# boardv2power.net
KiCad netlist of a schematic drawn in EAGLE
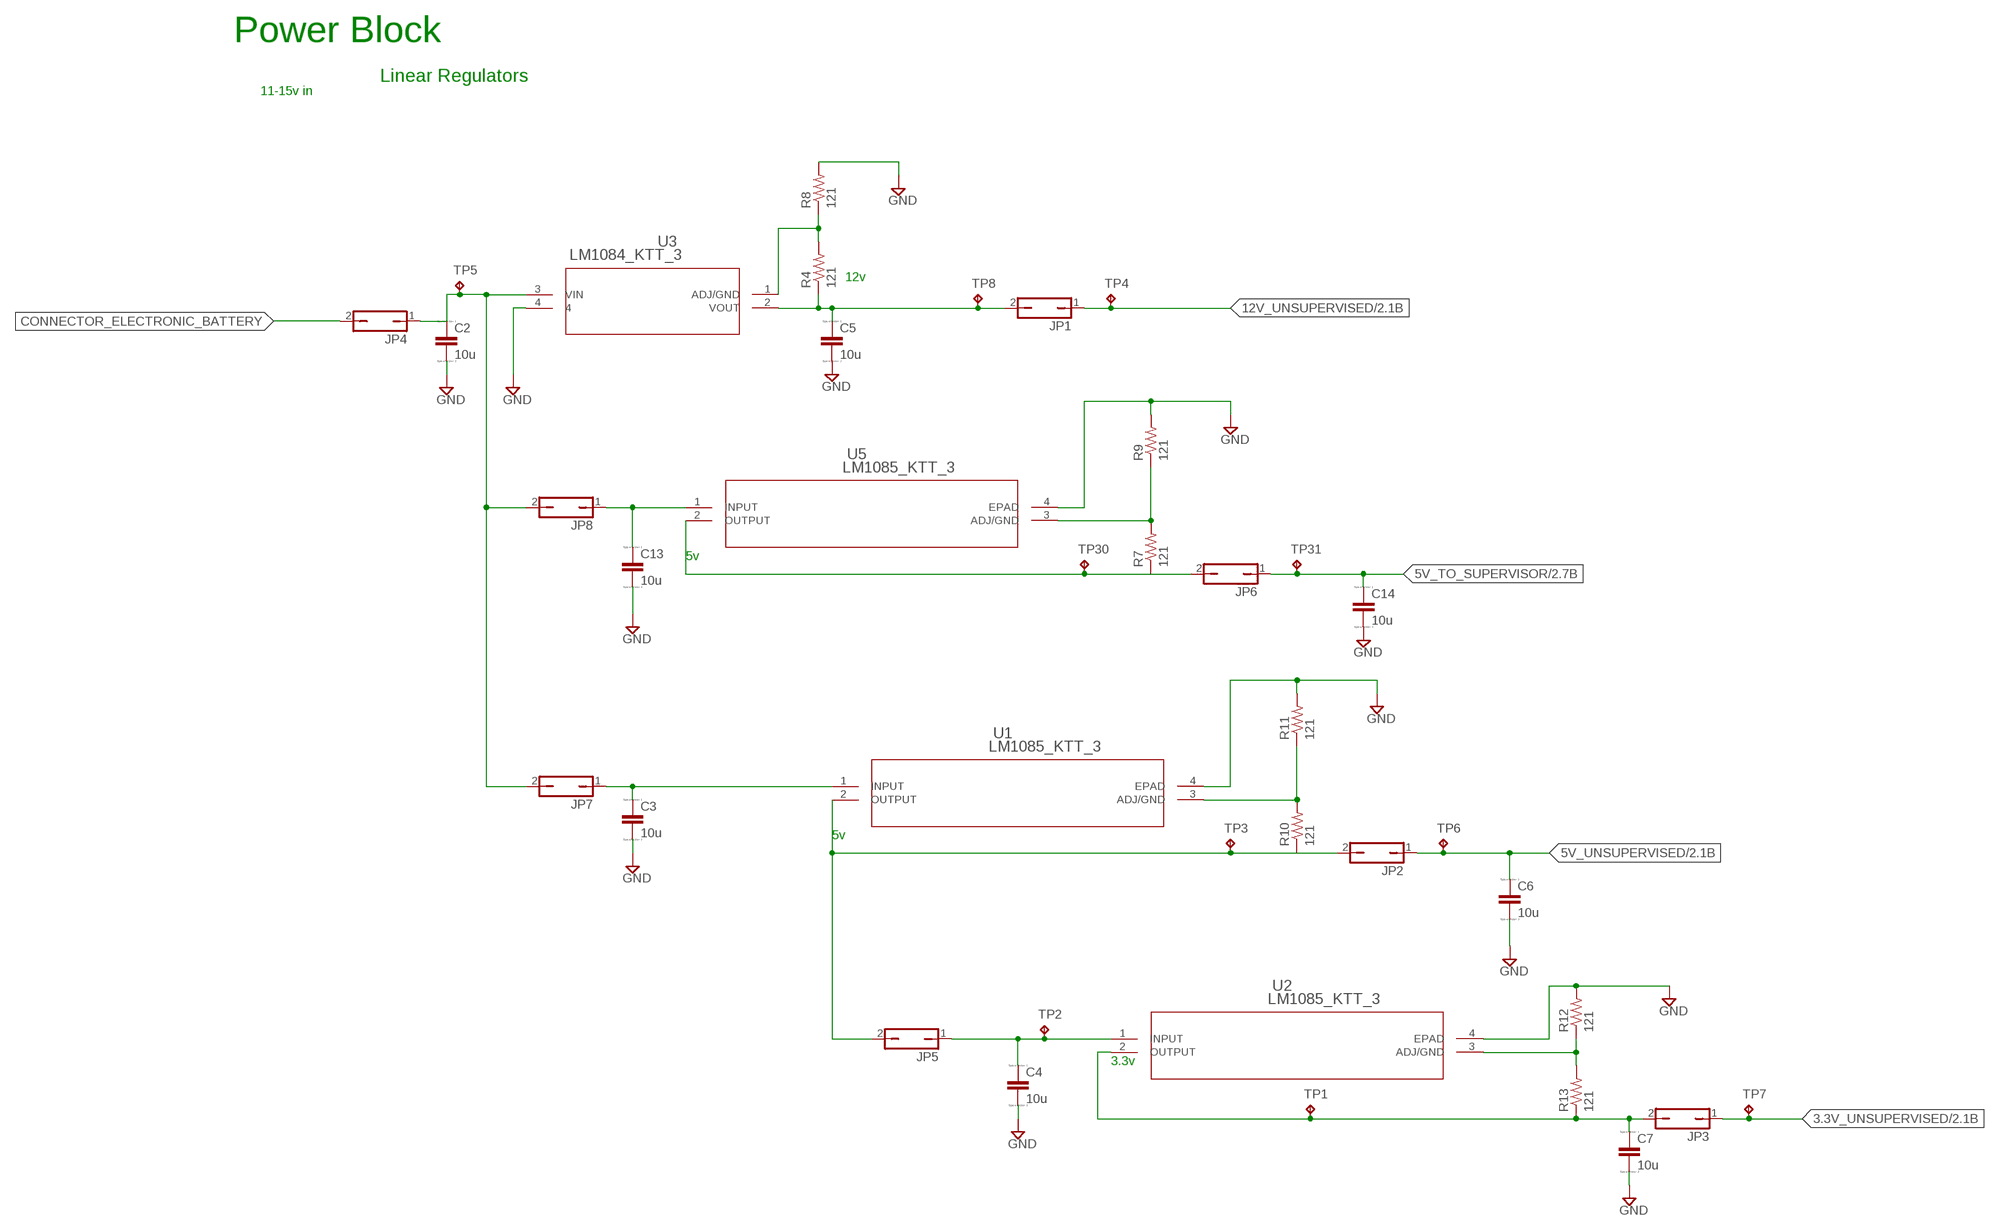
[diagram p0: schematic, sheet 1]
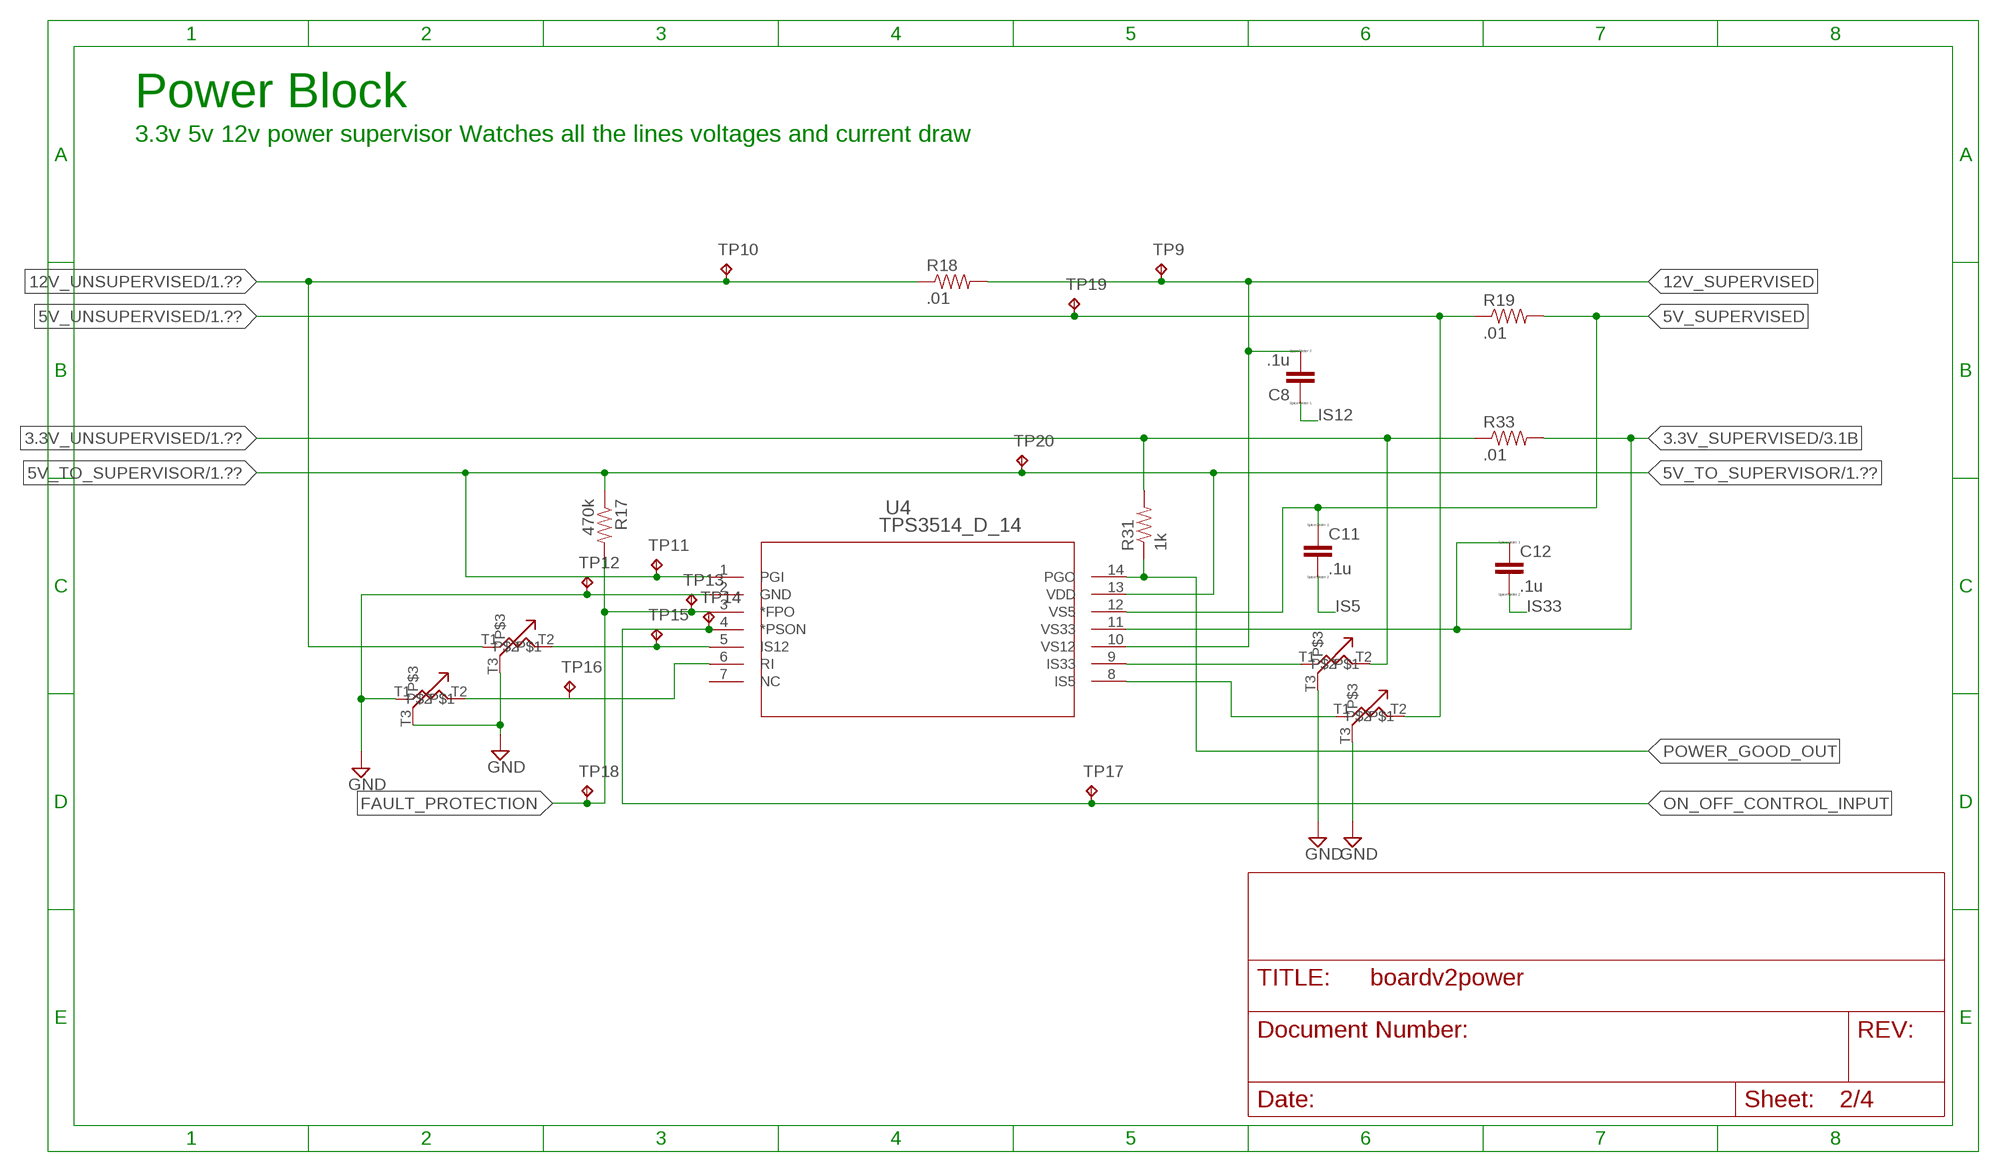
[diagram p1: schematic, sheet 2]
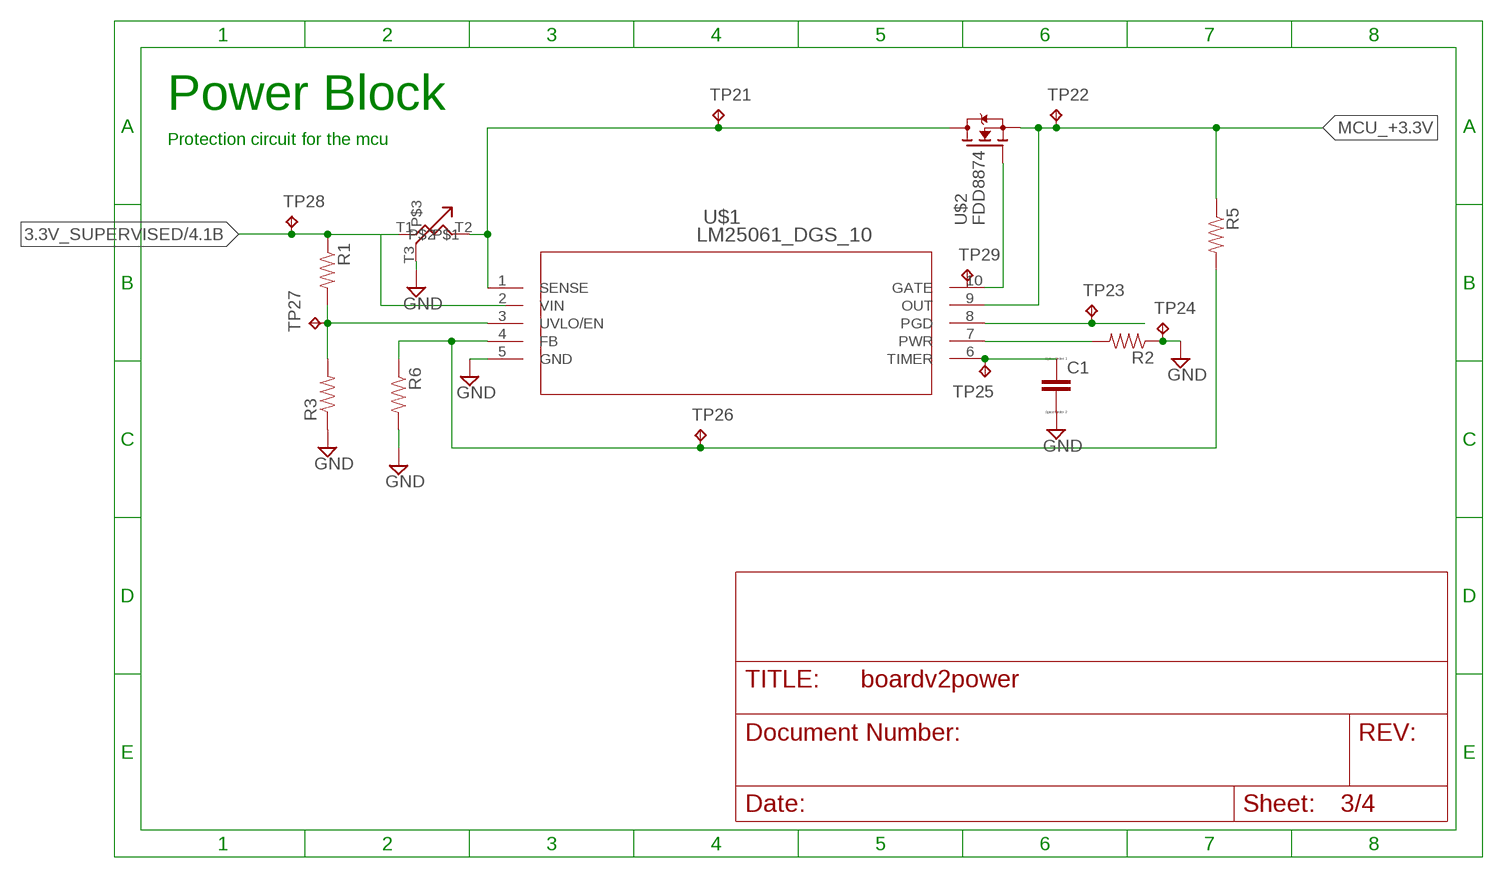
[diagram p2: schematic, sheet 3]
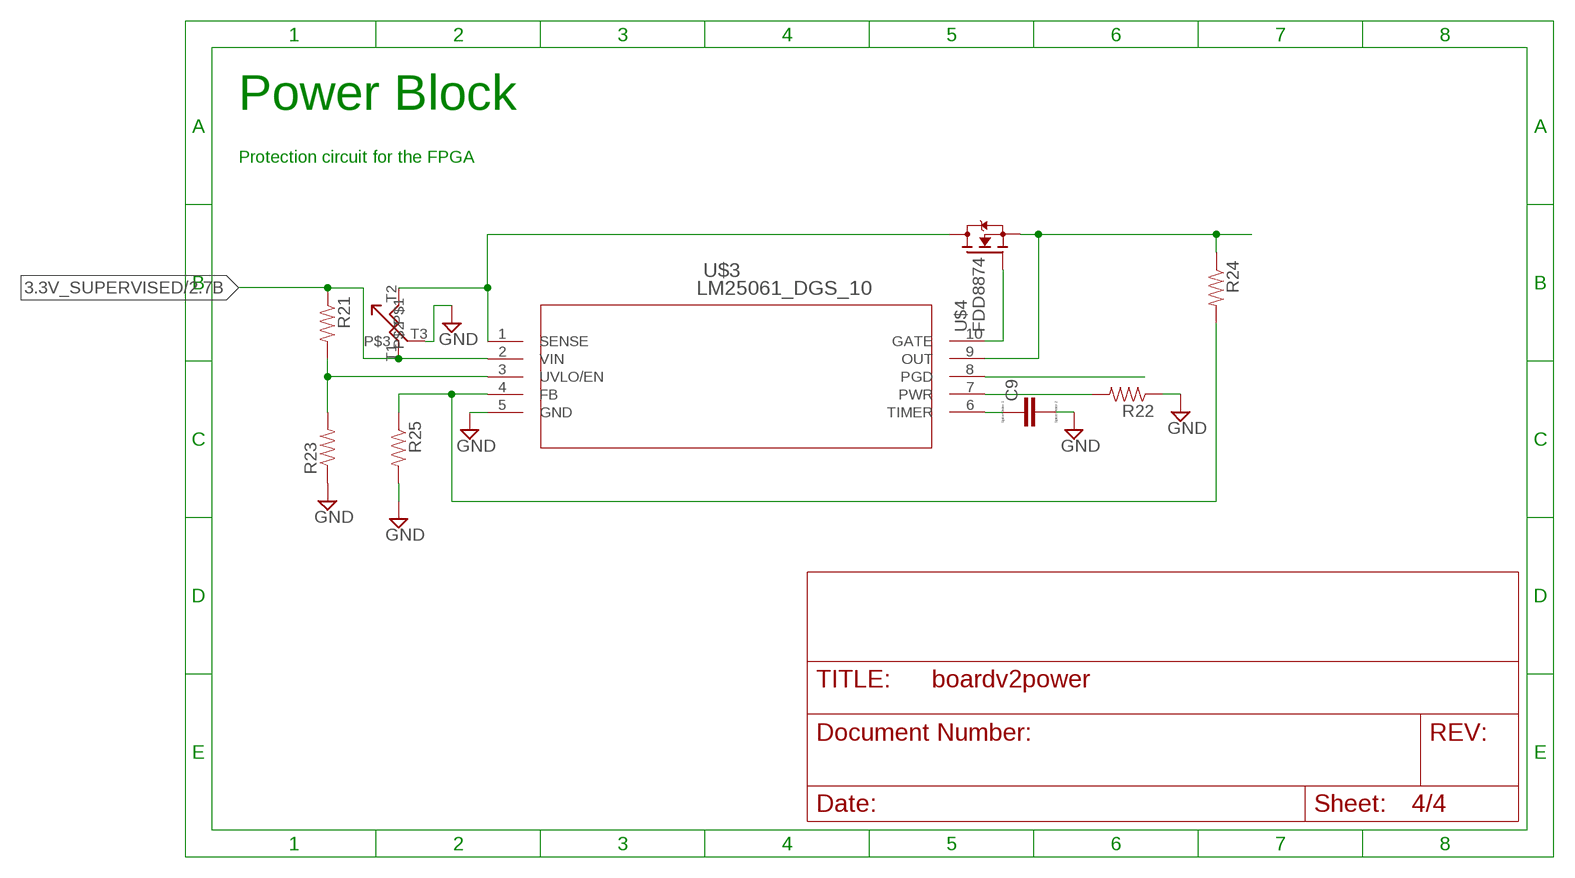
[diagram p3: schematic, sheet 4]

(export (version "E")
  (design (tool "Eeschema 10.0.6"))
  (components
    (comp (ref "C8")
      (value ".1u")
      (footprint "eagle-import:C0603")
      (libsource (lib "eagle-import") (part "CC0603"))
    )
    (comp (ref "C11")
      (value ".1u")
      (footprint "eagle-import:C0603")
      (libsource (lib "eagle-import") (part "CC0603"))
    )
    (comp (ref "C12")
      (value ".1u")
      (footprint "eagle-import:C0603")
      (libsource (lib "eagle-import") (part "CC0603"))
    )
    (comp (ref "R17")
      (value "470k")
      (footprint "eagle-import:0603-RES")
      (libsource (lib "eagle-import") (part "RESISTOR0603-RES"))
    )
    (comp (ref "R18")
      (value ".01")
      (footprint "eagle-import:0603-RES")
      (libsource (lib "eagle-import") (part "RESISTOR0603-RES"))
    )
    (comp (ref "R19")
      (value ".01")
      (footprint "eagle-import:0603-RES")
      (libsource (lib "eagle-import") (part "RESISTOR0603-RES"))
    )
    (comp (ref "R31")
      (value "1k")
      (footprint "eagle-import:0603-RES")
      (libsource (lib "eagle-import") (part "RESISTOR0603-RES"))
    )
    (comp (ref "R33")
      (value ".01")
      (footprint "eagle-import:0603-RES")
      (libsource (lib "eagle-import") (part "RESISTOR0603-RES"))
    )
    (comp (ref "TP9")
      (value "TPB1,27")
      (footprint "eagle-import:B1,27")
      (libsource (lib "eagle-import") (part "TPB1,27"))
    )
    (comp (ref "TP10")
      (value "TPB1,27")
      (footprint "eagle-import:B1,27")
      (libsource (lib "eagle-import") (part "TPB1,27"))
    )
    (comp (ref "TP11")
      (value "TPB1,27")
      (footprint "eagle-import:B1,27")
      (libsource (lib "eagle-import") (part "TPB1,27"))
    )
    (comp (ref "TP12")
      (value "TPB1,27")
      (footprint "eagle-import:B1,27")
      (libsource (lib "eagle-import") (part "TPB1,27"))
    )
    (comp (ref "TP13")
      (value "TPB1,27")
      (footprint "eagle-import:B1,27")
      (libsource (lib "eagle-import") (part "TPB1,27"))
    )
    (comp (ref "TP14")
      (value "TPB1,27")
      (footprint "eagle-import:B1,27")
      (libsource (lib "eagle-import") (part "TPB1,27"))
    )
    (comp (ref "TP15")
      (value "TPB1,27")
      (footprint "eagle-import:B1,27")
      (libsource (lib "eagle-import") (part "TPB1,27"))
    )
    (comp (ref "TP16")
      (value "TPB1,27")
      (footprint "eagle-import:B1,27")
      (libsource (lib "eagle-import") (part "TPB1,27"))
    )
    (comp (ref "TP17")
      (value "TPB1,27")
      (footprint "eagle-import:B1,27")
      (libsource (lib "eagle-import") (part "TPB1,27"))
    )
    (comp (ref "TP18")
      (value "TPB1,27")
      (footprint "eagle-import:B1,27")
      (libsource (lib "eagle-import") (part "TPB1,27"))
    )
    (comp (ref "TP19")
      (value "TPB1,27")
      (footprint "eagle-import:B1,27")
      (libsource (lib "eagle-import") (part "TPB1,27"))
    )
    (comp (ref "TP20")
      (value "TPB1,27")
      (footprint "eagle-import:B1,27")
      (libsource (lib "eagle-import") (part "TPB1,27"))
    )
    (comp (ref "U$7")
      (value "PVZ3A")
      (footprint "eagle-import:PVZ3A")
      (libsource (lib "eagle-import") (part "PVZ3A"))
    )
    (comp (ref "U$8")
      (value "PVZ3A")
      (footprint "eagle-import:PVZ3A")
      (libsource (lib "eagle-import") (part "PVZ3A"))
    )
    (comp (ref "U$9")
      (value "PVZ3A")
      (footprint "eagle-import:PVZ3A")
      (libsource (lib "eagle-import") (part "PVZ3A"))
    )
    (comp (ref "U$17")
      (value "PVZ3A")
      (footprint "eagle-import:PVZ3A")
      (libsource (lib "eagle-import") (part "PVZ3A"))
    )
    (comp (ref "U4")
      (value "TPS3514_D_14")
      (footprint "eagle-import:D14")
      (fields
        (field (name "GENERIC_PART_NUMBER") "TPS3514")
        (field (name "MANUFACTURER") "Texas Instruments")
        (field (name "MANUFACTURER_PART_NUMBER") "tps3514_d_14")
      )
      (libsource (lib "eagle-import") (part "TPS3514_D_14"))
    )
    (comp (ref "C9")
      (value "CC0603")
      (footprint "eagle-import:C0603")
      (libsource (lib "eagle-import") (part "CC0603"))
    )
    (comp (ref "R21")
      (value "RESISTOR0603-RES")
      (footprint "eagle-import:0603-RES")
      (libsource (lib "eagle-import") (part "RESISTOR0603-RES"))
    )
    (comp (ref "R22")
      (value "RESISTOR0603-RES")
      (footprint "eagle-import:0603-RES")
      (libsource (lib "eagle-import") (part "RESISTOR0603-RES"))
    )
    (comp (ref "R23")
      (value "RESISTOR0603-RES")
      (footprint "eagle-import:0603-RES")
      (libsource (lib "eagle-import") (part "RESISTOR0603-RES"))
    )
    (comp (ref "R24")
      (value "RESISTOR0603-RES")
      (footprint "eagle-import:0603-RES")
      (libsource (lib "eagle-import") (part "RESISTOR0603-RES"))
    )
    (comp (ref "R25")
      (value "RESISTOR0603-RES")
      (footprint "eagle-import:0603-RES")
      (libsource (lib "eagle-import") (part "RESISTOR0603-RES"))
    )
    (comp (ref "U$3")
      (value "LM25061_DGS_10")
      (footprint "eagle-import:MUB10A")
      (fields (field (name "MANUFACTURER_PART_NUMBER") "lm25061pmm-1nopb"))
      (libsource (lib "eagle-import") (part "LM25061_DGS_10"))
    )
    (comp (ref "U$4")
      (value "FDD8874")
      (footprint "eagle-import:TO252")
      (libsource (lib "eagle-import") (part "FDD8874"))
    )
    (comp (ref "U$16")
      (value "PVG3A")
      (footprint "eagle-import:PVZ3A")
      (libsource (lib "eagle-import") (part "PVG3A"))
    )
    (comp (ref "C2")
      (value "10u")
      (footprint "eagle-import:C0603")
      (libsource (lib "eagle-import") (part "CC0603"))
    )
    (comp (ref "C3")
      (value "10u")
      (footprint "eagle-import:C0603")
      (libsource (lib "eagle-import") (part "CC0603"))
    )
    (comp (ref "C4")
      (value "10u")
      (footprint "eagle-import:C0603")
      (libsource (lib "eagle-import") (part "CC0603"))
    )
    (comp (ref "C5")
      (value "10u")
      (footprint "eagle-import:C0603")
      (libsource (lib "eagle-import") (part "CC0603"))
    )
    (comp (ref "C6")
      (value "10u")
      (footprint "eagle-import:C0603")
      (libsource (lib "eagle-import") (part "CC0603"))
    )
    (comp (ref "C7")
      (value "10u")
      (footprint "eagle-import:C0603")
      (libsource (lib "eagle-import") (part "CC0603"))
    )
    (comp (ref "C13")
      (value "10u")
      (footprint "eagle-import:C0603")
      (libsource (lib "eagle-import") (part "CC0603"))
    )
    (comp (ref "C14")
      (value "10u")
      (footprint "eagle-import:C0603")
      (libsource (lib "eagle-import") (part "CC0603"))
    )
    (comp (ref "JP1")
      (value "JP1Q")
      (footprint "eagle-import:JP1")
      (libsource (lib "eagle-import") (part "JP1Q"))
    )
    (comp (ref "JP2")
      (value "JP1Q")
      (footprint "eagle-import:JP1")
      (libsource (lib "eagle-import") (part "JP1Q"))
    )
    (comp (ref "JP3")
      (value "JP1Q")
      (footprint "eagle-import:JP1")
      (libsource (lib "eagle-import") (part "JP1Q"))
    )
    (comp (ref "JP4")
      (value "JP1Q")
      (footprint "eagle-import:JP1")
      (libsource (lib "eagle-import") (part "JP1Q"))
    )
    (comp (ref "JP5")
      (value "JP1Q")
      (footprint "eagle-import:JP1")
      (libsource (lib "eagle-import") (part "JP1Q"))
    )
    (comp (ref "JP6")
      (value "JP1Q")
      (footprint "eagle-import:JP1")
      (libsource (lib "eagle-import") (part "JP1Q"))
    )
    (comp (ref "JP7")
      (value "JP1Q")
      (footprint "eagle-import:JP1")
      (libsource (lib "eagle-import") (part "JP1Q"))
    )
    (comp (ref "JP8")
      (value "JP1Q")
      (footprint "eagle-import:JP1")
      (libsource (lib "eagle-import") (part "JP1Q"))
    )
    (comp (ref "R4")
      (value "121")
      (footprint "eagle-import:0603-RES")
      (libsource (lib "eagle-import") (part "RESISTOR0603-RES"))
    )
    (comp (ref "R7")
      (value "121")
      (footprint "eagle-import:0603-RES")
      (libsource (lib "eagle-import") (part "RESISTOR0603-RES"))
    )
    (comp (ref "R8")
      (value "121")
      (footprint "eagle-import:0603-RES")
      (libsource (lib "eagle-import") (part "RESISTOR0603-RES"))
    )
    (comp (ref "R9")
      (value "121")
      (footprint "eagle-import:0603-RES")
      (libsource (lib "eagle-import") (part "RESISTOR0603-RES"))
    )
    (comp (ref "R10")
      (value "121")
      (footprint "eagle-import:0603-RES")
      (libsource (lib "eagle-import") (part "RESISTOR0603-RES"))
    )
    (comp (ref "R11")
      (value "121")
      (footprint "eagle-import:0603-RES")
      (libsource (lib "eagle-import") (part "RESISTOR0603-RES"))
    )
    (comp (ref "R12")
      (value "121")
      (footprint "eagle-import:0603-RES")
      (libsource (lib "eagle-import") (part "RESISTOR0603-RES"))
    )
    (comp (ref "R13")
      (value "121")
      (footprint "eagle-import:0603-RES")
      (libsource (lib "eagle-import") (part "RESISTOR0603-RES"))
    )
    (comp (ref "TP1")
      (value "TPB1,27")
      (footprint "eagle-import:B1,27")
      (libsource (lib "eagle-import") (part "TPB1,27"))
    )
    (comp (ref "TP2")
      (value "TPB1,27")
      (footprint "eagle-import:B1,27")
      (libsource (lib "eagle-import") (part "TPB1,27"))
    )
    (comp (ref "TP3")
      (value "TPB1,27")
      (footprint "eagle-import:B1,27")
      (libsource (lib "eagle-import") (part "TPB1,27"))
    )
    (comp (ref "TP4")
      (value "TPB1,27")
      (footprint "eagle-import:B1,27")
      (libsource (lib "eagle-import") (part "TPB1,27"))
    )
    (comp (ref "TP5")
      (value "TPB1,27")
      (footprint "eagle-import:B1,27")
      (libsource (lib "eagle-import") (part "TPB1,27"))
    )
    (comp (ref "TP6")
      (value "TPB1,27")
      (footprint "eagle-import:B1,27")
      (libsource (lib "eagle-import") (part "TPB1,27"))
    )
    (comp (ref "TP7")
      (value "TPB1,27")
      (footprint "eagle-import:B1,27")
      (libsource (lib "eagle-import") (part "TPB1,27"))
    )
    (comp (ref "TP8")
      (value "TPB1,27")
      (footprint "eagle-import:B1,27")
      (libsource (lib "eagle-import") (part "TPB1,27"))
    )
    (comp (ref "TP30")
      (value "TPB1,27")
      (footprint "eagle-import:B1,27")
      (libsource (lib "eagle-import") (part "TPB1,27"))
    )
    (comp (ref "TP31")
      (value "TPB1,27")
      (footprint "eagle-import:B1,27")
      (libsource (lib "eagle-import") (part "TPB1,27"))
    )
    (comp (ref "U1")
      (value "LM1085_KTT_3")
      (footprint "eagle-import:KTT3")
      (fields (field (name "MANUFACTURER_PART_NUMBER") "lm1085_ktt_3"))
      (libsource (lib "eagle-import") (part "LM1085_KTT_3"))
    )
    (comp (ref "U2")
      (value "LM1085_KTT_3")
      (footprint "eagle-import:KTT3")
      (fields (field (name "MANUFACTURER_PART_NUMBER") "lm1085_ktt_3"))
      (libsource (lib "eagle-import") (part "LM1085_KTT_3"))
    )
    (comp (ref "U3")
      (value "LM1084_KTT_3")
      (footprint "eagle-import:TS3B")
      (fields (field (name "PARTNUMBER") "LM1084IS-33"))
      (libsource (lib "eagle-import") (part "LM1084_KTT_3"))
    )
    (comp (ref "U5")
      (value "LM1085_KTT_3")
      (footprint "eagle-import:KTT3")
      (fields (field (name "MANUFACTURER_PART_NUMBER") "lm1085_ktt_3"))
      (libsource (lib "eagle-import") (part "LM1085_KTT_3"))
    )
    (comp (ref "C1")
      (value "CC0603")
      (footprint "eagle-import:C0603")
      (libsource (lib "eagle-import") (part "CC0603"))
    )
    (comp (ref "R1")
      (value "RESISTOR0603-RES")
      (footprint "eagle-import:0603-RES")
      (libsource (lib "eagle-import") (part "RESISTOR0603-RES"))
    )
    (comp (ref "R2")
      (value "RESISTOR0603-RES")
      (footprint "eagle-import:0603-RES")
      (libsource (lib "eagle-import") (part "RESISTOR0603-RES"))
    )
    (comp (ref "R3")
      (value "RESISTOR0603-RES")
      (footprint "eagle-import:0603-RES")
      (libsource (lib "eagle-import") (part "RESISTOR0603-RES"))
    )
    (comp (ref "R5")
      (value "RESISTOR0603-RES")
      (footprint "eagle-import:0603-RES")
      (libsource (lib "eagle-import") (part "RESISTOR0603-RES"))
    )
    (comp (ref "R6")
      (value "RESISTOR0603-RES")
      (footprint "eagle-import:0603-RES")
      (libsource (lib "eagle-import") (part "RESISTOR0603-RES"))
    )
    (comp (ref "TP21")
      (value "TPB1,27")
      (footprint "eagle-import:B1,27")
      (libsource (lib "eagle-import") (part "TPB1,27"))
    )
    (comp (ref "TP22")
      (value "TPB1,27")
      (footprint "eagle-import:B1,27")
      (libsource (lib "eagle-import") (part "TPB1,27"))
    )
    (comp (ref "TP23")
      (value "TPB1,27")
      (footprint "eagle-import:B1,27")
      (libsource (lib "eagle-import") (part "TPB1,27"))
    )
    (comp (ref "TP24")
      (value "TPB1,27")
      (footprint "eagle-import:B1,27")
      (libsource (lib "eagle-import") (part "TPB1,27"))
    )
    (comp (ref "TP25")
      (value "TPB1,27")
      (footprint "eagle-import:B1,27")
      (libsource (lib "eagle-import") (part "TPB1,27"))
    )
    (comp (ref "TP26")
      (value "TPB1,27")
      (footprint "eagle-import:B1,27")
      (libsource (lib "eagle-import") (part "TPB1,27"))
    )
    (comp (ref "TP27")
      (value "TPB1,27")
      (footprint "eagle-import:B1,27")
      (libsource (lib "eagle-import") (part "TPB1,27"))
    )
    (comp (ref "TP28")
      (value "TPB1,27")
      (footprint "eagle-import:B1,27")
      (libsource (lib "eagle-import") (part "TPB1,27"))
    )
    (comp (ref "TP29")
      (value "TPB1,27")
      (footprint "eagle-import:B1,27")
      (libsource (lib "eagle-import") (part "TPB1,27"))
    )
    (comp (ref "U$1")
      (value "LM25061_DGS_10")
      (footprint "eagle-import:MUB10A")
      (fields (field (name "MANUFACTURER_PART_NUMBER") "lm25061pmm-1nopb"))
      (libsource (lib "eagle-import") (part "LM25061_DGS_10"))
    )
    (comp (ref "U$2")
      (value "FDD8874")
      (footprint "eagle-import:TO252")
      (libsource (lib "eagle-import") (part "FDD8874"))
    )
    (comp (ref "U$14")
      (value "PVG3A")
      (footprint "eagle-import:PVZ3A")
      (libsource (lib "eagle-import") (part "PVG3A"))
    )
  )
  (nets
    (net (code "1") (name "3.3V_SUPERVISED") (class "Default")
      (node (ref "C12") (pin "1") (pinfunction "1_1") (pintype "passive"))
      (node (ref "R1") (pin "1") (pinfunction "1_1") (pintype "passive"))
      (node (ref "R21") (pin "1") (pinfunction "1_1") (pintype "passive"))
      (node (ref "R33") (pin "2") (pinfunction "2_2") (pintype "passive"))
      (node (ref "TP28") (pin "TP") (pinfunction "TP_TP") (pintype "input"))
      (node (ref "U$14") (pin "T1") (pinfunction "P$1_T1") (pintype "bidirectional"))
      (node (ref "U$16") (pin "T1") (pinfunction "P$1_T1") (pintype "bidirectional"))
      (node (ref "U$3") (pin "2") (pinfunction "VIN_2") (pintype "power_in"))
      (node (ref "U4") (pin "11") (pinfunction "VS33_11") (pintype "input"))
    )
    (net (code "2") (name "3.3V_UNSUPERVISED") (class "Default")
      (node (ref "JP3") (pin "1") (pinfunction "1_1") (pintype "passive"))
      (node (ref "R31") (pin "2") (pinfunction "2_2") (pintype "passive"))
      (node (ref "R33") (pin "1") (pinfunction "1_1") (pintype "passive"))
      (node (ref "TP7") (pin "TP") (pinfunction "TP_TP") (pintype "input"))
      (node (ref "U$8") (pin "T2") (pinfunction "P$2_T2") (pintype "bidirectional"))
    )
    (net (code "3") (name "5V_SUPERVISED") (class "Default")
      (node (ref "C11") (pin "1") (pinfunction "1_1") (pintype "passive"))
      (node (ref "R19") (pin "2") (pinfunction "2_2") (pintype "passive"))
      (node (ref "U4") (pin "12") (pinfunction "VS5_12") (pintype "input"))
    )
    (net (code "4") (name "5V_TO_SUPERVISOR") (class "Default")
      (node (ref "C14") (pin "1") (pinfunction "1_1") (pintype "passive"))
      (node (ref "JP6") (pin "1") (pinfunction "1_1") (pintype "passive"))
      (node (ref "R17") (pin "1") (pinfunction "1_1") (pintype "passive"))
      (node (ref "TP11") (pin "TP") (pinfunction "TP_TP") (pintype "input"))
      (node (ref "TP20") (pin "TP") (pinfunction "TP_TP") (pintype "input"))
      (node (ref "TP31") (pin "TP") (pinfunction "TP_TP") (pintype "input"))
      (node (ref "U4") (pin "1") (pinfunction "PGI_1") (pintype "input"))
      (node (ref "U4") (pin "13") (pinfunction "VDD_13") (pintype "input"))
    )
    (net (code "5") (name "5V_UNSUPERVISED") (class "Default")
      (node (ref "C6") (pin "1") (pinfunction "1_1") (pintype "passive"))
      (node (ref "JP2") (pin "1") (pinfunction "1_1") (pintype "passive"))
      (node (ref "R19") (pin "1") (pinfunction "1_1") (pintype "passive"))
      (node (ref "TP19") (pin "TP") (pinfunction "TP_TP") (pintype "input"))
      (node (ref "TP6") (pin "TP") (pinfunction "TP_TP") (pintype "input"))
      (node (ref "U$9") (pin "T2") (pinfunction "P$2_T2") (pintype "bidirectional"))
    )
    (net (code "6") (name "12V_SUPERVISED") (class "Default")
      (node (ref "C8") (pin "2") (pinfunction "2_2") (pintype "passive"))
      (node (ref "R18") (pin "2") (pinfunction "2_2") (pintype "passive"))
      (node (ref "TP9") (pin "TP") (pinfunction "TP_TP") (pintype "input"))
      (node (ref "U4") (pin "10") (pinfunction "VS12_10") (pintype "input"))
    )
    (net (code "7") (name "12V_UNSUPERVISED") (class "Default")
      (node (ref "JP1") (pin "1") (pinfunction "1_1") (pintype "passive"))
      (node (ref "R18") (pin "1") (pinfunction "1_1") (pintype "passive"))
      (node (ref "TP10") (pin "TP") (pinfunction "TP_TP") (pintype "input"))
      (node (ref "TP4") (pin "TP") (pinfunction "TP_TP") (pintype "input"))
      (node (ref "U$7") (pin "T1") (pinfunction "P$1_T1") (pintype "bidirectional"))
    )
    (net (code "8") (name "CONNECTOR_ELECTRONIC_BATTERY") (class "Default")
      (node (ref "JP4") (pin "2") (pinfunction "2_2") (pintype "passive"))
    )
    (net (code "9") (name "FAULT_PROTECTION") (class "Default")
      (node (ref "R17") (pin "2") (pinfunction "2_2") (pintype "passive"))
      (node (ref "TP13") (pin "TP") (pinfunction "TP_TP") (pintype "input"))
      (node (ref "TP18") (pin "TP") (pinfunction "TP_TP") (pintype "input"))
      (node (ref "U4") (pin "3") (pinfunction "*FPO_3") (pintype "output"))
    )
    (net (code "10") (name "GND") (class "Default")
      (node (ref "C1") (pin "2") (pinfunction "2_2") (pintype "passive"))
      (node (ref "C13") (pin "2") (pinfunction "2_2") (pintype "passive"))
      (node (ref "C14") (pin "2") (pinfunction "2_2") (pintype "passive"))
      (node (ref "C2") (pin "2") (pinfunction "2_2") (pintype "passive"))
      (node (ref "C3") (pin "2") (pinfunction "2_2") (pintype "passive"))
      (node (ref "C4") (pin "2") (pinfunction "2_2") (pintype "passive"))
      (node (ref "C5") (pin "2") (pinfunction "2_2") (pintype "passive"))
      (node (ref "C6") (pin "2") (pinfunction "2_2") (pintype "passive"))
      (node (ref "C7") (pin "2") (pinfunction "2_2") (pintype "passive"))
      (node (ref "C9") (pin "2") (pinfunction "2_2") (pintype "passive"))
      (node (ref "R11") (pin "2") (pinfunction "2_2") (pintype "passive"))
      (node (ref "R12") (pin "2") (pinfunction "2_2") (pintype "passive"))
      (node (ref "R2") (pin "1") (pinfunction "1_1") (pintype "passive"))
      (node (ref "R22") (pin "1") (pinfunction "1_1") (pintype "passive"))
      (node (ref "R23") (pin "1") (pinfunction "1_1") (pintype "passive"))
      (node (ref "R25") (pin "2") (pinfunction "2_2") (pintype "passive"))
      (node (ref "R3") (pin "1") (pinfunction "1_1") (pintype "passive"))
      (node (ref "R6") (pin "2") (pinfunction "2_2") (pintype "passive"))
      (node (ref "R8") (pin "2") (pinfunction "2_2") (pintype "passive"))
      (node (ref "R9") (pin "2") (pinfunction "2_2") (pintype "passive"))
      (node (ref "TP12") (pin "TP") (pinfunction "TP_TP") (pintype "input"))
      (node (ref "TP24") (pin "TP") (pinfunction "TP_TP") (pintype "input"))
      (node (ref "U$1") (pin "5") (pinfunction "GND_5") (pintype "power_in"))
      (node (ref "U$14") (pin "T3") (pinfunction "P$3_T3") (pintype "bidirectional"))
      (node (ref "U$16") (pin "T3") (pinfunction "P$3_T3") (pintype "bidirectional"))
      (node (ref "U$17") (pin "T1") (pinfunction "P$1_T1") (pintype "bidirectional"))
      (node (ref "U$17") (pin "T3") (pinfunction "P$3_T3") (pintype "bidirectional"))
      (node (ref "U$3") (pin "5") (pinfunction "GND_5") (pintype "power_in"))
      (node (ref "U$7") (pin "T3") (pinfunction "P$3_T3") (pintype "bidirectional"))
      (node (ref "U$8") (pin "T3") (pinfunction "P$3_T3") (pintype "bidirectional"))
      (node (ref "U$9") (pin "T3") (pinfunction "P$3_T3") (pintype "bidirectional"))
      (node (ref "U1") (pin "4") (pinfunction "EPAD_4") (pintype "passive"))
      (node (ref "U2") (pin "4") (pinfunction "EPAD_4") (pintype "passive"))
      (node (ref "U3") (pin "4") (pinfunction "4_4") (pintype "passive"))
      (node (ref "U4") (pin "2") (pinfunction "GND_2") (pintype "power_in"))
      (node (ref "U5") (pin "4") (pinfunction "EPAD_4") (pintype "passive"))
    )
    (net (code "11") (name "IS5") (class "Default")
      (node (ref "C11") (pin "2") (pinfunction "2_2") (pintype "passive"))
      (node (ref "U$9") (pin "T1") (pinfunction "P$1_T1") (pintype "bidirectional"))
      (node (ref "U4") (pin "8") (pinfunction "IS5_8") (pintype "input"))
    )
    (net (code "12") (name "IS12") (class "Default")
      (node (ref "C8") (pin "1") (pinfunction "1_1") (pintype "passive"))
      (node (ref "TP15") (pin "TP") (pinfunction "TP_TP") (pintype "input"))
      (node (ref "U$7") (pin "T2") (pinfunction "P$2_T2") (pintype "bidirectional"))
      (node (ref "U4") (pin "5") (pinfunction "IS12_5") (pintype "input"))
    )
    (net (code "13") (name "IS33") (class "Default")
      (node (ref "C12") (pin "2") (pinfunction "2_2") (pintype "passive"))
      (node (ref "U$8") (pin "T1") (pinfunction "P$1_T1") (pintype "bidirectional"))
      (node (ref "U4") (pin "9") (pinfunction "IS33_9") (pintype "input"))
    )
    (net (code "14") (name "MCU_+3.3V") (class "Default")
      (node (ref "R5") (pin "1") (pinfunction "1_1") (pintype "passive"))
      (node (ref "TP22") (pin "TP") (pinfunction "TP_TP") (pintype "input"))
      (node (ref "U$1") (pin "9") (pinfunction "OUT_9") (pintype "power_in"))
      (node (ref "U$2") (pin "4") (pinfunction "S_4") (pintype "passive"))
    )
    (net (code "15") (name "Net-(U$1-FB)") (class "Default")
      (node (ref "R5") (pin "2") (pinfunction "2_2") (pintype "passive"))
      (node (ref "R6") (pin "1") (pinfunction "1_1") (pintype "passive"))
      (node (ref "TP26") (pin "TP") (pinfunction "TP_TP") (pintype "input"))
      (node (ref "U$1") (pin "4") (pinfunction "FB_4") (pintype "input"))
    )
    (net (code "16") (name "Net-(U$1-GATE)") (class "Default")
      (node (ref "U$1") (pin "10") (pinfunction "GATE_10") (pintype "output"))
      (node (ref "U$2") (pin "1") (pinfunction "G_1") (pintype "passive"))
    )
    (net (code "17") (name "Net-(U$1-PGD)") (class "Default")
      (node (ref "TP23") (pin "TP") (pinfunction "TP_TP") (pintype "input"))
      (node (ref "U$1") (pin "8") (pinfunction "PGD_8") (pintype "passive"))
    )
    (net (code "18") (name "Net-(U$1-PWR)") (class "Default")
      (node (ref "R2") (pin "2") (pinfunction "2_2") (pintype "passive"))
      (node (ref "U$1") (pin "7") (pinfunction "PWR_7") (pintype "input"))
    )
    (net (code "19") (name "Net-(U$1-SENSE)") (class "Default")
      (node (ref "TP21") (pin "TP") (pinfunction "TP_TP") (pintype "input"))
      (node (ref "U$1") (pin "1") (pinfunction "SENSE_1") (pintype "input"))
      (node (ref "U$14") (pin "T2") (pinfunction "P$2_T2") (pintype "bidirectional"))
      (node (ref "U$2") (pin "3") (pinfunction "D_3") (pintype "passive"))
    )
    (net (code "20") (name "Net-(U$1-TIMER)") (class "Default")
      (node (ref "C1") (pin "1") (pinfunction "1_1") (pintype "passive"))
      (node (ref "TP25") (pin "TP") (pinfunction "TP_TP") (pintype "input"))
      (node (ref "U$1") (pin "6") (pinfunction "TIMER_6") (pintype "input"))
    )
    (net (code "21") (name "Net-(U$1-UVLO{slash}EN)") (class "Default")
      (node (ref "R1") (pin "2") (pinfunction "2_2") (pintype "passive"))
      (node (ref "R3") (pin "2") (pinfunction "2_2") (pintype "passive"))
      (node (ref "TP27") (pin "TP") (pinfunction "TP_TP") (pintype "input"))
      (node (ref "U$1") (pin "3") (pinfunction "UVLO/EN_3") (pintype "input"))
    )
    (net (code "22") (name "Net-(U$3-FB)") (class "Default")
      (node (ref "R24") (pin "2") (pinfunction "2_2") (pintype "passive"))
      (node (ref "R25") (pin "1") (pinfunction "1_1") (pintype "passive"))
      (node (ref "U$3") (pin "4") (pinfunction "FB_4") (pintype "input"))
    )
    (net (code "23") (name "Net-(U$3-GATE)") (class "Default")
      (node (ref "U$3") (pin "10") (pinfunction "GATE_10") (pintype "output"))
      (node (ref "U$4") (pin "1") (pinfunction "G_1") (pintype "passive"))
    )
    (net (code "24") (name "Net-(U$3-OUT)") (class "Default")
      (node (ref "R24") (pin "1") (pinfunction "1_1") (pintype "passive"))
      (node (ref "U$3") (pin "9") (pinfunction "OUT_9") (pintype "power_in"))
      (node (ref "U$4") (pin "4") (pinfunction "S_4") (pintype "passive"))
    )
    (net (code "25") (name "Net-(U$3-PWR)") (class "Default")
      (node (ref "R22") (pin "2") (pinfunction "2_2") (pintype "passive"))
      (node (ref "U$3") (pin "7") (pinfunction "PWR_7") (pintype "input"))
    )
    (net (code "26") (name "Net-(U$3-TIMER)") (class "Default")
      (node (ref "C9") (pin "1") (pinfunction "1_1") (pintype "passive"))
      (node (ref "U$3") (pin "6") (pinfunction "TIMER_6") (pintype "input"))
    )
    (net (code "27") (name "Net-(U$3-UVLO{slash}EN)") (class "Default")
      (node (ref "R21") (pin "2") (pinfunction "2_2") (pintype "passive"))
      (node (ref "R23") (pin "2") (pinfunction "2_2") (pintype "passive"))
      (node (ref "U$3") (pin "3") (pinfunction "UVLO/EN_3") (pintype "input"))
    )
    (net (code "28") (name "Net-(U$16-P$2)") (class "Default")
      (node (ref "U$16") (pin "T2") (pinfunction "P$2_T2") (pintype "bidirectional"))
      (node (ref "U$3") (pin "1") (pinfunction "SENSE_1") (pintype "input"))
      (node (ref "U$4") (pin "3") (pinfunction "D_3") (pintype "passive"))
    )
    (net (code "29") (name "Net-(U$17-P$2)") (class "Default")
      (node (ref "TP16") (pin "TP") (pinfunction "TP_TP") (pintype "input"))
      (node (ref "U$17") (pin "T2") (pinfunction "P$2_T2") (pintype "bidirectional"))
      (node (ref "U4") (pin "6") (pinfunction "RI_6") (pintype "input"))
    )
    (net (code "30") (name "Net-(U1-ADJ{slash}GND)") (class "Default")
      (node (ref "R10") (pin "2") (pinfunction "2_2") (pintype "passive"))
      (node (ref "R11") (pin "1") (pinfunction "1_1") (pintype "passive"))
      (node (ref "U1") (pin "3") (pinfunction "ADJ/GND_3") (pintype "passive"))
    )
    (net (code "31") (name "Net-(U1-INPUT)") (class "Default")
      (node (ref "C3") (pin "1") (pinfunction "1_1") (pintype "passive"))
      (node (ref "JP7") (pin "1") (pinfunction "1_1") (pintype "passive"))
      (node (ref "U1") (pin "1") (pinfunction "INPUT_1") (pintype "input"))
    )
    (net (code "32") (name "Net-(U1-OUTPUT)") (class "Default")
      (node (ref "JP2") (pin "2") (pinfunction "2_2") (pintype "passive"))
      (node (ref "JP5") (pin "2") (pinfunction "2_2") (pintype "passive"))
      (node (ref "R10") (pin "1") (pinfunction "1_1") (pintype "passive"))
      (node (ref "TP3") (pin "TP") (pinfunction "TP_TP") (pintype "input"))
      (node (ref "U1") (pin "2") (pinfunction "OUTPUT_2") (pintype "output"))
    )
    (net (code "33") (name "Net-(U2-ADJ{slash}GND)") (class "Default")
      (node (ref "R12") (pin "1") (pinfunction "1_1") (pintype "passive"))
      (node (ref "R13") (pin "2") (pinfunction "2_2") (pintype "passive"))
      (node (ref "U2") (pin "3") (pinfunction "ADJ/GND_3") (pintype "passive"))
    )
    (net (code "34") (name "Net-(U2-INPUT)") (class "Default")
      (node (ref "C4") (pin "1") (pinfunction "1_1") (pintype "passive"))
      (node (ref "JP5") (pin "1") (pinfunction "1_1") (pintype "passive"))
      (node (ref "TP2") (pin "TP") (pinfunction "TP_TP") (pintype "input"))
      (node (ref "U2") (pin "1") (pinfunction "INPUT_1") (pintype "input"))
    )
    (net (code "35") (name "Net-(U2-OUTPUT)") (class "Default")
      (node (ref "C7") (pin "1") (pinfunction "1_1") (pintype "passive"))
      (node (ref "JP3") (pin "2") (pinfunction "2_2") (pintype "passive"))
      (node (ref "R13") (pin "1") (pinfunction "1_1") (pintype "passive"))
      (node (ref "TP1") (pin "TP") (pinfunction "TP_TP") (pintype "input"))
      (node (ref "U2") (pin "2") (pinfunction "OUTPUT_2") (pintype "output"))
    )
    (net (code "36") (name "Net-(U3-ADJ{slash}GND)") (class "Default")
      (node (ref "R4") (pin "2") (pinfunction "2_2") (pintype "passive"))
      (node (ref "R8") (pin "1") (pinfunction "1_1") (pintype "passive"))
      (node (ref "U3") (pin "1") (pinfunction "ADJ/GND_1") (pintype "passive"))
    )
    (net (code "37") (name "Net-(U3-VIN)") (class "Default")
      (node (ref "C2") (pin "1") (pinfunction "1_1") (pintype "passive"))
      (node (ref "JP4") (pin "1") (pinfunction "1_1") (pintype "passive"))
      (node (ref "JP7") (pin "2") (pinfunction "2_2") (pintype "passive"))
      (node (ref "JP8") (pin "2") (pinfunction "2_2") (pintype "passive"))
      (node (ref "TP5") (pin "TP") (pinfunction "TP_TP") (pintype "input"))
      (node (ref "U3") (pin "3") (pinfunction "VIN_3") (pintype "input"))
    )
    (net (code "38") (name "Net-(U3-VOUT)") (class "Default")
      (node (ref "C5") (pin "1") (pinfunction "1_1") (pintype "passive"))
      (node (ref "JP1") (pin "2") (pinfunction "2_2") (pintype "passive"))
      (node (ref "R4") (pin "1") (pinfunction "1_1") (pintype "passive"))
      (node (ref "TP8") (pin "TP") (pinfunction "TP_TP") (pintype "input"))
      (node (ref "U3") (pin "2") (pinfunction "VOUT_2") (pintype "output"))
    )
    (net (code "39") (name "Net-(U5-ADJ{slash}GND)") (class "Default")
      (node (ref "R7") (pin "2") (pinfunction "2_2") (pintype "passive"))
      (node (ref "R9") (pin "1") (pinfunction "1_1") (pintype "passive"))
      (node (ref "U5") (pin "3") (pinfunction "ADJ/GND_3") (pintype "passive"))
    )
    (net (code "40") (name "Net-(U5-INPUT)") (class "Default")
      (node (ref "C13") (pin "1") (pinfunction "1_1") (pintype "passive"))
      (node (ref "JP8") (pin "1") (pinfunction "1_1") (pintype "passive"))
      (node (ref "U5") (pin "1") (pinfunction "INPUT_1") (pintype "input"))
    )
    (net (code "41") (name "Net-(U5-OUTPUT)") (class "Default")
      (node (ref "JP6") (pin "2") (pinfunction "2_2") (pintype "passive"))
      (node (ref "R7") (pin "1") (pinfunction "1_1") (pintype "passive"))
      (node (ref "TP30") (pin "TP") (pinfunction "TP_TP") (pintype "input"))
      (node (ref "U5") (pin "2") (pinfunction "OUTPUT_2") (pintype "output"))
    )
    (net (code "42") (name "ON_OFF_CONTROL_INPUT") (class "Default")
      (node (ref "TP14") (pin "TP") (pinfunction "TP_TP") (pintype "input"))
      (node (ref "TP17") (pin "TP") (pinfunction "TP_TP") (pintype "input"))
      (node (ref "U4") (pin "4") (pinfunction "*PSON_4") (pintype "input"))
    )
    (net (code "43") (name "POWER_GOOD_OUT") (class "Default")
      (node (ref "R31") (pin "1") (pinfunction "1_1") (pintype "passive"))
      (node (ref "U4") (pin "14") (pinfunction "PGO_14") (pintype "output"))
    )
    (net (code "44") (name "VIN") (class "Default")
      (node (ref "U$1") (pin "2") (pinfunction "VIN_2") (pintype "power_in"))
    )
    (net (code "45") (name "unconnected-(TP29-PadTP)") (class "Default")
      (node (ref "TP29") (pin "TP") (pinfunction "TP_TP") (pintype "input"))
    )
    (net (code "46") (name "unconnected-(U$3-PGD-Pad8)") (class "Default")
      (node (ref "U$3") (pin "8") (pinfunction "PGD_8") (pintype "passive"))
    )
    (net (code "47") (name "unconnected-(U4-NC-Pad7)") (class "Default")
      (node (ref "U4") (pin "7") (pinfunction "NC_7") (pintype "passive"))
    )
  )
)
